# Processor_Interface.net
KiCad netlist of a schematic drawn in Altium Designer
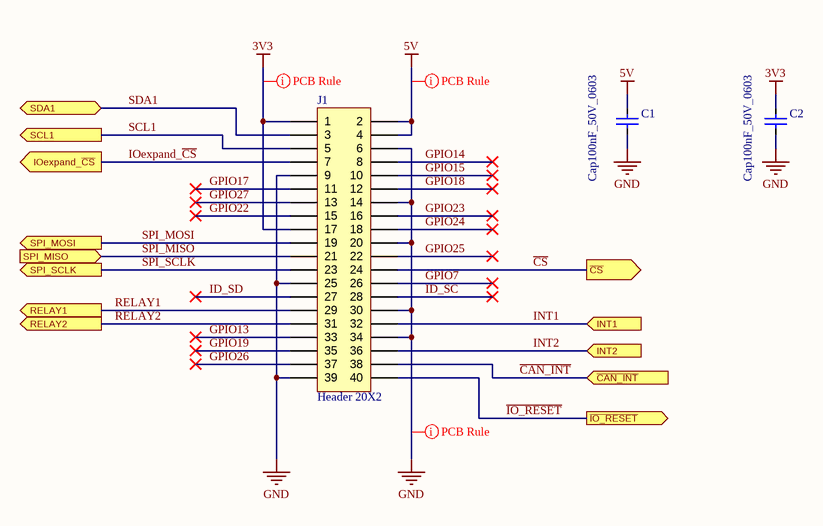
[diagram p0: Processor_Interface.SchDoc]

(export (version "E")
  (design (tool "Eeschema 10.0.6"))
  (components
    (comp (ref "C1")
      (value "Cap100nF_50V_0603")
      (footprint "0603C_L")
      (libsource (lib " Advanced] Training Course - A365") (part "CAP General"))
    )
    (comp (ref "C2")
      (value "Cap100nF_50V_0603")
      (footprint "0603C_L")
      (libsource (lib " Advanced] Training Course - A365") (part "CAP General"))
    )
    (comp (ref "J1")
      (value "Header 20X2")
      (footprint "HDR2X20")
      (description "Header, 20-Pin, Dual row")
      (fields (field (name "PUBLISHER") "Altium Limited") (field (name "SOURCE") "WCT.SchLib"))
      (libsource (lib " Advanced] Training Course - A365") (part "Header 20X2"))
    )
  )
  (nets
    (net (code "1") (name "/CAN_INT") (class "Default")
      (node (ref "J1") (pin "38") (pinfunction "38_38") (pintype "passive"))
    )
    (net (code "2") (name "/GPIO7") (class "Default")
      (node (ref "J1") (pin "26") (pinfunction "26_26") (pintype "passive+no_connect"))
    )
    (net (code "3") (name "/GPIO13") (class "Default")
      (node (ref "J1") (pin "33") (pinfunction "33_33") (pintype "passive+no_connect"))
    )
    (net (code "4") (name "/GPIO14") (class "Default")
      (node (ref "J1") (pin "8") (pinfunction "8_8") (pintype "passive+no_connect"))
    )
    (net (code "5") (name "/GPIO15") (class "Default")
      (node (ref "J1") (pin "10") (pinfunction "10_10") (pintype "passive+no_connect"))
    )
    (net (code "6") (name "/GPIO17") (class "Default")
      (node (ref "J1") (pin "11") (pinfunction "11_11") (pintype "passive+no_connect"))
    )
    (net (code "7") (name "/GPIO18") (class "Default")
      (node (ref "J1") (pin "12") (pinfunction "12_12") (pintype "passive+no_connect"))
    )
    (net (code "8") (name "/GPIO19") (class "Default")
      (node (ref "J1") (pin "35") (pinfunction "35_35") (pintype "passive+no_connect"))
    )
    (net (code "9") (name "/GPIO22") (class "Default")
      (node (ref "J1") (pin "15") (pinfunction "15_15") (pintype "passive+no_connect"))
    )
    (net (code "10") (name "/GPIO23") (class "Default")
      (node (ref "J1") (pin "16") (pinfunction "16_16") (pintype "passive+no_connect"))
    )
    (net (code "11") (name "/GPIO24") (class "Default")
      (node (ref "J1") (pin "18") (pinfunction "18_18") (pintype "passive+no_connect"))
    )
    (net (code "12") (name "/GPIO25") (class "Default")
      (node (ref "J1") (pin "22") (pinfunction "22_22") (pintype "passive+no_connect"))
    )
    (net (code "13") (name "/GPIO26") (class "Default")
      (node (ref "J1") (pin "37") (pinfunction "37_37") (pintype "passive+no_connect"))
    )
    (net (code "14") (name "/GPIO27") (class "Default")
      (node (ref "J1") (pin "13") (pinfunction "13_13") (pintype "passive+no_connect"))
    )
    (net (code "15") (name "/ID_SC") (class "Default")
      (node (ref "J1") (pin "28") (pinfunction "28_28") (pintype "passive+no_connect"))
    )
    (net (code "16") (name "/ID_SD") (class "Default")
      (node (ref "J1") (pin "27") (pinfunction "27_27") (pintype "passive+no_connect"))
    )
    (net (code "17") (name "/INT1") (class "Default")
      (node (ref "J1") (pin "32") (pinfunction "32_32") (pintype "passive"))
    )
    (net (code "18") (name "/INT2") (class "Default")
      (node (ref "J1") (pin "36") (pinfunction "36_36") (pintype "passive"))
    )
    (net (code "19") (name "/IO_RESET") (class "Default")
      (node (ref "J1") (pin "40") (pinfunction "40_40") (pintype "passive"))
    )
    (net (code "20") (name "/IOexpand_~{CS}") (class "Default")
      (node (ref "J1") (pin "7") (pinfunction "7_7") (pintype "passive"))
    )
    (net (code "21") (name "/RELAY1") (class "Default")
      (node (ref "J1") (pin "29") (pinfunction "29_29") (pintype "passive"))
    )
    (net (code "22") (name "/RELAY2") (class "Default")
      (node (ref "J1") (pin "31") (pinfunction "31_31") (pintype "passive"))
    )
    (net (code "23") (name "/SCL1") (class "Default")
      (node (ref "J1") (pin "5") (pinfunction "5_5") (pintype "passive"))
    )
    (net (code "24") (name "/SDA1") (class "Default")
      (node (ref "J1") (pin "3") (pinfunction "3_3") (pintype "passive"))
    )
    (net (code "25") (name "/SPI_MISO") (class "Default")
      (node (ref "J1") (pin "21") (pinfunction "21_21") (pintype "passive"))
    )
    (net (code "26") (name "/SPI_MOSI") (class "Default")
      (node (ref "J1") (pin "19") (pinfunction "19_19") (pintype "passive"))
    )
    (net (code "27") (name "/SPI_SCLK") (class "Default")
      (node (ref "J1") (pin "23") (pinfunction "23_23") (pintype "passive"))
    )
    (net (code "28") (name "/~{CS}") (class "Default")
      (node (ref "J1") (pin "24") (pinfunction "24_24") (pintype "passive"))
    )
    (net (code "29") (name "3V3") (class "Default")
      (node (ref "C2") (pin "2") (pinfunction "2_2") (pintype "passive"))
      (node (ref "J1") (pin "1") (pinfunction "1_1") (pintype "passive"))
      (node (ref "J1") (pin "17") (pinfunction "17_17") (pintype "passive"))
    )
    (net (code "30") (name "5V") (class "Default")
      (node (ref "C1") (pin "2") (pinfunction "2_2") (pintype "passive"))
      (node (ref "J1") (pin "2") (pinfunction "2_2") (pintype "passive"))
      (node (ref "J1") (pin "4") (pinfunction "4_4") (pintype "passive"))
    )
    (net (code "31") (name "GND") (class "Default")
      (node (ref "C1") (pin "1") (pinfunction "1_1") (pintype "passive"))
      (node (ref "C2") (pin "1") (pinfunction "1_1") (pintype "passive"))
      (node (ref "J1") (pin "14") (pinfunction "14_14") (pintype "passive"))
      (node (ref "J1") (pin "20") (pinfunction "20_20") (pintype "passive"))
      (node (ref "J1") (pin "25") (pinfunction "25_25") (pintype "passive"))
      (node (ref "J1") (pin "30") (pinfunction "30_30") (pintype "passive"))
      (node (ref "J1") (pin "34") (pinfunction "34_34") (pintype "passive"))
      (node (ref "J1") (pin "39") (pinfunction "39_39") (pintype "passive"))
      (node (ref "J1") (pin "6") (pinfunction "6_6") (pintype "passive"))
      (node (ref "J1") (pin "9") (pinfunction "9_9") (pintype "passive"))
    )
  )
)
